# GPSBreakoutBoard.net
KiCad netlist of a schematic drawn in EAGLE
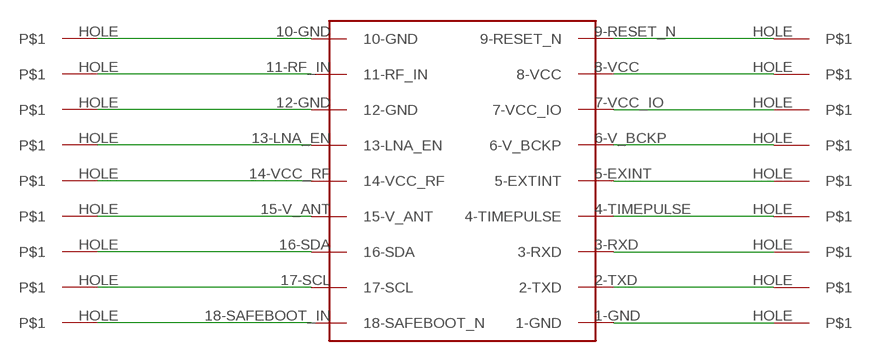
[diagram p0: schematic, sheet 1]

(export (version "E")
  (design (tool "Eeschema 10.0.6"))
  (components
    (comp (ref "U$1")
      (value "GPS_DEVICE")
      (footprint "eagle-import:GPSMOUNT")
      (libsource (lib "eagle-import") (part "GPS_DEVICE"))
    )
    (comp (ref "U$2")
      (value "HOLE")
      (footprint "eagle-import:THING")
      (libsource (lib "eagle-import") (part "HOLE"))
    )
    (comp (ref "U$3")
      (value "HOLE")
      (footprint "eagle-import:THING")
      (libsource (lib "eagle-import") (part "HOLE"))
    )
    (comp (ref "U$4")
      (value "HOLE")
      (footprint "eagle-import:THING")
      (libsource (lib "eagle-import") (part "HOLE"))
    )
    (comp (ref "U$5")
      (value "HOLE")
      (footprint "eagle-import:THING")
      (libsource (lib "eagle-import") (part "HOLE"))
    )
    (comp (ref "U$6")
      (value "HOLE")
      (footprint "eagle-import:THING")
      (libsource (lib "eagle-import") (part "HOLE"))
    )
    (comp (ref "U$7")
      (value "HOLE")
      (footprint "eagle-import:THING")
      (libsource (lib "eagle-import") (part "HOLE"))
    )
    (comp (ref "U$8")
      (value "HOLE")
      (footprint "eagle-import:THING")
      (libsource (lib "eagle-import") (part "HOLE"))
    )
    (comp (ref "U$9")
      (value "HOLE")
      (footprint "eagle-import:THING")
      (libsource (lib "eagle-import") (part "HOLE"))
    )
    (comp (ref "U$10")
      (value "HOLE")
      (footprint "eagle-import:THING")
      (libsource (lib "eagle-import") (part "HOLE"))
    )
    (comp (ref "U$11")
      (value "HOLE")
      (footprint "eagle-import:THING")
      (libsource (lib "eagle-import") (part "HOLE"))
    )
    (comp (ref "U$12")
      (value "HOLE")
      (footprint "eagle-import:THING")
      (libsource (lib "eagle-import") (part "HOLE"))
    )
    (comp (ref "U$13")
      (value "HOLE")
      (footprint "eagle-import:THING")
      (libsource (lib "eagle-import") (part "HOLE"))
    )
    (comp (ref "U$14")
      (value "HOLE")
      (footprint "eagle-import:THING")
      (libsource (lib "eagle-import") (part "HOLE"))
    )
    (comp (ref "U$15")
      (value "HOLE")
      (footprint "eagle-import:THING")
      (libsource (lib "eagle-import") (part "HOLE"))
    )
    (comp (ref "U$16")
      (value "HOLE")
      (footprint "eagle-import:THING")
      (libsource (lib "eagle-import") (part "HOLE"))
    )
    (comp (ref "U$17")
      (value "HOLE")
      (footprint "eagle-import:THING")
      (libsource (lib "eagle-import") (part "HOLE"))
    )
    (comp (ref "U$18")
      (value "HOLE")
      (footprint "eagle-import:THING")
      (libsource (lib "eagle-import") (part "HOLE"))
    )
    (comp (ref "U$19")
      (value "HOLE")
      (footprint "eagle-import:THING")
      (libsource (lib "eagle-import") (part "HOLE"))
    )
  )
  (nets
    (net (code "1") (name "Net-(U$1-5-EXTINT)") (class "Default")
      (node (ref "U$1") (pin "5-EXINT") (pinfunction "5-EXTINT_5-EXINT") (pintype "bidirectional"))
      (node (ref "U$15") (pin "HOLE") (pinfunction "P$1_HOLE") (pintype "bidirectional"))
    )
    (net (code "2") (name "Net-(U$1-18-SAFEBOOT_N)") (class "Default")
      (node (ref "U$1") (pin "18-SAFEBOOT_IN") (pinfunction "18-SAFEBOOT_N_18-SAFEBOOT_IN") (pintype "bidirectional"))
      (node (ref "U$10") (pin "HOLE") (pinfunction "P$1_HOLE") (pintype "bidirectional"))
    )
    (net (code "3") (name "Net-(U$2-P$1)") (class "Default")
      (node (ref "U$1") (pin "10-GND") (pinfunction "10-GND_10-GND") (pintype "bidirectional"))
      (node (ref "U$2") (pin "HOLE") (pinfunction "P$1_HOLE") (pintype "bidirectional"))
    )
    (net (code "4") (name "Net-(U$3-P$1)") (class "Default")
      (node (ref "U$1") (pin "11-RF_IN") (pinfunction "11-RF_IN_11-RF_IN") (pintype "bidirectional"))
      (node (ref "U$3") (pin "HOLE") (pinfunction "P$1_HOLE") (pintype "bidirectional"))
    )
    (net (code "5") (name "Net-(U$4-P$1)") (class "Default")
      (node (ref "U$1") (pin "12-GND") (pinfunction "12-GND_12-GND") (pintype "bidirectional"))
      (node (ref "U$4") (pin "HOLE") (pinfunction "P$1_HOLE") (pintype "bidirectional"))
    )
    (net (code "6") (name "Net-(U$5-P$1)") (class "Default")
      (node (ref "U$1") (pin "13-LNA_EN") (pinfunction "13-LNA_EN_13-LNA_EN") (pintype "bidirectional"))
      (node (ref "U$5") (pin "HOLE") (pinfunction "P$1_HOLE") (pintype "bidirectional"))
    )
    (net (code "7") (name "Net-(U$6-P$1)") (class "Default")
      (node (ref "U$1") (pin "14-VCC_RF") (pinfunction "14-VCC_RF_14-VCC_RF") (pintype "bidirectional"))
      (node (ref "U$6") (pin "HOLE") (pinfunction "P$1_HOLE") (pintype "bidirectional"))
    )
    (net (code "8") (name "Net-(U$7-P$1)") (class "Default")
      (node (ref "U$1") (pin "15-V_ANT") (pinfunction "15-V_ANT_15-V_ANT") (pintype "bidirectional"))
      (node (ref "U$7") (pin "HOLE") (pinfunction "P$1_HOLE") (pintype "bidirectional"))
    )
    (net (code "9") (name "Net-(U$8-P$1)") (class "Default")
      (node (ref "U$1") (pin "16-SDA") (pinfunction "16-SDA_16-SDA") (pintype "bidirectional"))
      (node (ref "U$8") (pin "HOLE") (pinfunction "P$1_HOLE") (pintype "bidirectional"))
    )
    (net (code "10") (name "Net-(U$9-P$1)") (class "Default")
      (node (ref "U$1") (pin "17-SCL") (pinfunction "17-SCL_17-SCL") (pintype "bidirectional"))
      (node (ref "U$9") (pin "HOLE") (pinfunction "P$1_HOLE") (pintype "bidirectional"))
    )
    (net (code "11") (name "Net-(U$11-P$1)") (class "Default")
      (node (ref "U$1") (pin "9-RESET_N") (pinfunction "9-RESET_N_9-RESET_N") (pintype "bidirectional"))
      (node (ref "U$11") (pin "HOLE") (pinfunction "P$1_HOLE") (pintype "bidirectional"))
    )
    (net (code "12") (name "Net-(U$12-P$1)") (class "Default")
      (node (ref "U$1") (pin "8-VCC") (pinfunction "8-VCC_8-VCC") (pintype "bidirectional"))
      (node (ref "U$12") (pin "HOLE") (pinfunction "P$1_HOLE") (pintype "bidirectional"))
    )
    (net (code "13") (name "Net-(U$13-P$1)") (class "Default")
      (node (ref "U$1") (pin "7-VCC_IO") (pinfunction "7-VCC_IO_7-VCC_IO") (pintype "bidirectional"))
      (node (ref "U$13") (pin "HOLE") (pinfunction "P$1_HOLE") (pintype "bidirectional"))
    )
    (net (code "14") (name "Net-(U$14-P$1)") (class "Default")
      (node (ref "U$1") (pin "6-V_BCKP") (pinfunction "6-V_BCKP_6-V_BCKP") (pintype "bidirectional"))
      (node (ref "U$14") (pin "HOLE") (pinfunction "P$1_HOLE") (pintype "bidirectional"))
    )
    (net (code "15") (name "Net-(U$16-P$1)") (class "Default")
      (node (ref "U$1") (pin "4-TIMEPULSE") (pinfunction "4-TIMEPULSE_4-TIMEPULSE") (pintype "bidirectional"))
      (node (ref "U$16") (pin "HOLE") (pinfunction "P$1_HOLE") (pintype "bidirectional"))
    )
    (net (code "16") (name "Net-(U$17-P$1)") (class "Default")
      (node (ref "U$1") (pin "3-RXD") (pinfunction "3-RXD_3-RXD") (pintype "bidirectional"))
      (node (ref "U$17") (pin "HOLE") (pinfunction "P$1_HOLE") (pintype "bidirectional"))
    )
    (net (code "17") (name "Net-(U$18-P$1)") (class "Default")
      (node (ref "U$1") (pin "2-TXD") (pinfunction "2-TXD_2-TXD") (pintype "bidirectional"))
      (node (ref "U$18") (pin "HOLE") (pinfunction "P$1_HOLE") (pintype "bidirectional"))
    )
    (net (code "18") (name "Net-(U$19-P$1)") (class "Default")
      (node (ref "U$1") (pin "1-GND") (pinfunction "1-GND_1-GND") (pintype "bidirectional"))
      (node (ref "U$19") (pin "HOLE") (pinfunction "P$1_HOLE") (pintype "bidirectional"))
    )
  )
)
